# MASTER_HW.net
KiCad netlist of a schematic drawn in Altium Designer
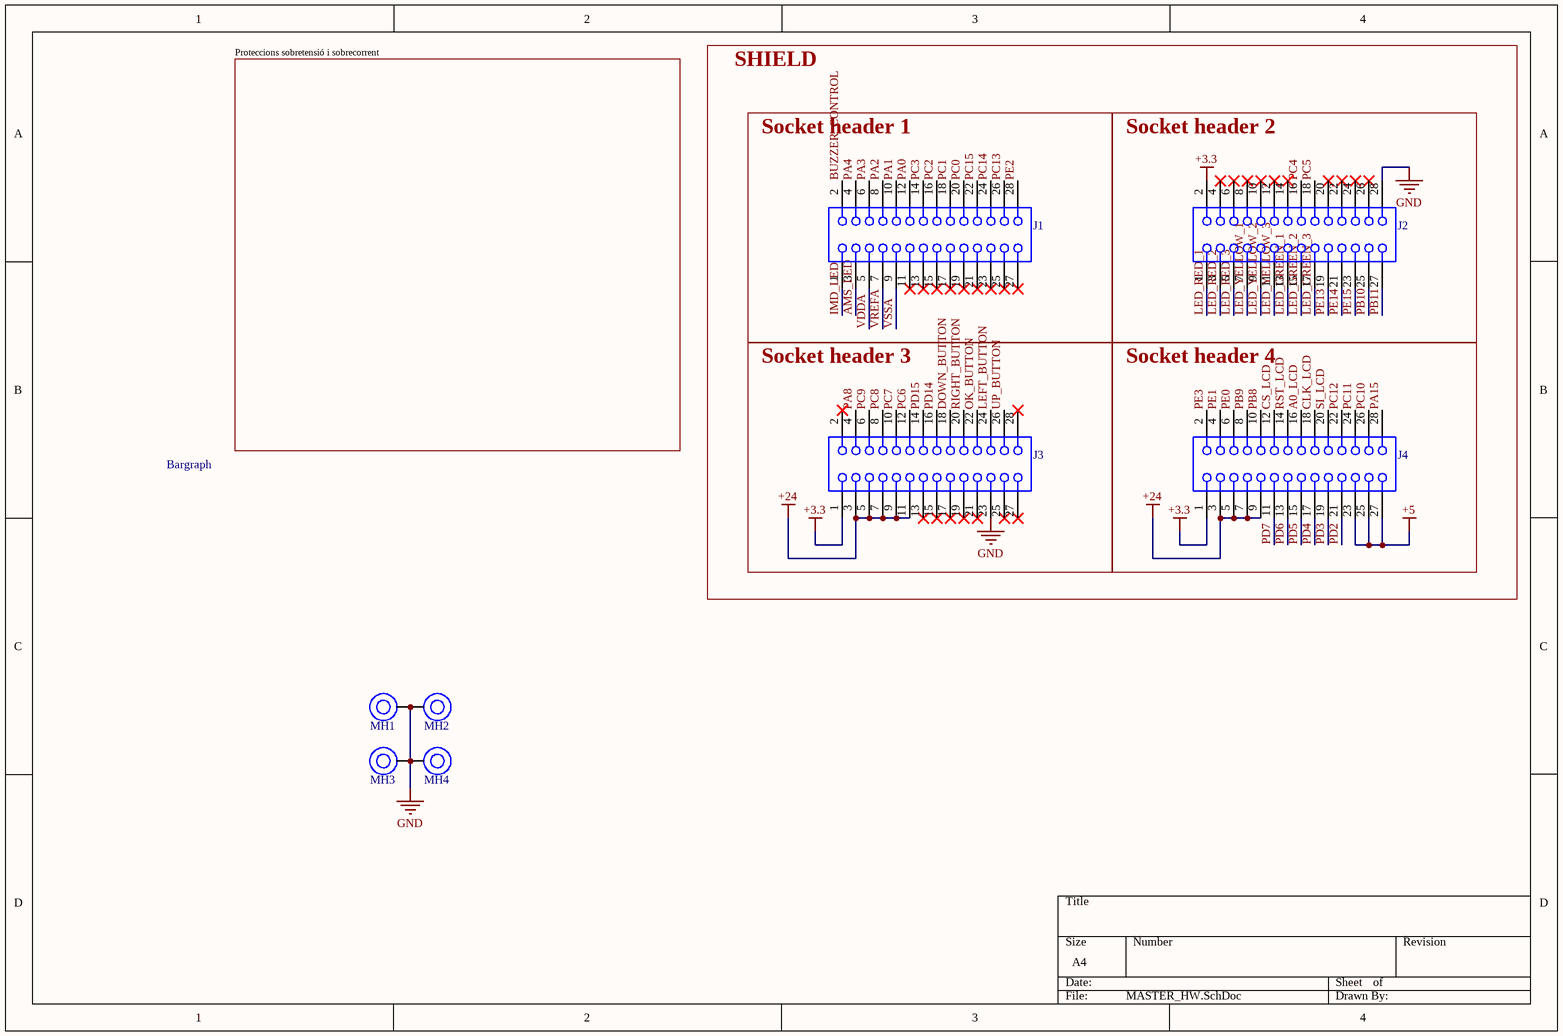
[diagram p0: MASTER_HW.SchDoc]

(export (version "E")
  (design (tool "Eeschema 10.0.6"))
  (components
    (comp (ref "J1")
      (value "62332821021")
      (footprint "62332821021")
      (description "WR-PHD Socket Header, SMT, Vertical, pitch 1.27mm, 2 Row, 28P")
      (fields (field (name "MANUFACTURER") "Wurth Elektronik"))
      (libsource (lib "Electromechanical") (part "62332821021"))
    )
    (comp (ref "J2")
      (value "62332821021")
      (footprint "62332821021")
      (description "WR-PHD Socket Header, SMT, Vertical, pitch 1.27mm, 2 Row, 28P")
      (fields (field (name "MANUFACTURER") "Wurth Elektronik"))
      (libsource (lib "Electromechanical") (part "62332821021"))
    )
    (comp (ref "J3")
      (value "62332821021")
      (footprint "62332821021")
      (description "WR-PHD Socket Header, SMT, Vertical, pitch 1.27mm, 2 Row, 28P")
      (fields (field (name "MANUFACTURER") "Wurth Elektronik"))
      (libsource (lib "Electromechanical") (part "62332821021"))
    )
    (comp (ref "J4")
      (value "62332821021")
      (footprint "62332821021")
      (description "WR-PHD Socket Header, SMT, Vertical, pitch 1.27mm, 2 Row, 28P")
      (fields (field (name "MANUFACTURER") "Wurth Elektronik"))
      (libsource (lib "Electromechanical") (part "62332821021"))
    )
    (comp (ref "MH1")
      (value "Mounting_Hole_M3")
      (footprint "Mounting_Hole_M3")
      (libsource (lib "Electromechanical") (part "Mounting_Hole_M3"))
    )
    (comp (ref "MH2")
      (value "Mounting_Hole_M3")
      (footprint "Mounting_Hole_M3")
      (libsource (lib "Electromechanical") (part "Mounting_Hole_M3"))
    )
    (comp (ref "MH3")
      (value "Mounting_Hole_M3")
      (footprint "Mounting_Hole_M3")
      (libsource (lib "Electromechanical") (part "Mounting_Hole_M3"))
    )
    (comp (ref "MH4")
      (value "Mounting_Hole_M3")
      (footprint "Mounting_Hole_M3")
      (libsource (lib "Electromechanical") (part "Mounting_Hole_M3"))
    )
  )
  (nets
    (net (code "1") (name "+3.3") (class "Default")
      (node (ref "J2") (pin "2") (pinfunction "2_2") (pintype "passive"))
      (node (ref "J3") (pin "1") (pinfunction "1_1") (pintype "passive"))
      (node (ref "J4") (pin "1") (pinfunction "1_1") (pintype "passive"))
    )
    (net (code "2") (name "+5") (class "Default")
      (node (ref "J4") (pin "23") (pinfunction "23_23") (pintype "passive"))
      (node (ref "J4") (pin "25") (pinfunction "25_25") (pintype "passive"))
      (node (ref "J4") (pin "27") (pinfunction "27_27") (pintype "passive"))
    )
    (net (code "3") (name "+24") (class "Default")
      (node (ref "J3") (pin "11") (pinfunction "11_11") (pintype "passive"))
      (node (ref "J3") (pin "3") (pinfunction "3_3") (pintype "passive"))
      (node (ref "J3") (pin "5") (pinfunction "5_5") (pintype "passive"))
      (node (ref "J3") (pin "7") (pinfunction "7_7") (pintype "passive"))
      (node (ref "J3") (pin "9") (pinfunction "9_9") (pintype "passive"))
      (node (ref "J4") (pin "3") (pinfunction "3_3") (pintype "passive"))
      (node (ref "J4") (pin "5") (pinfunction "5_5") (pintype "passive"))
      (node (ref "J4") (pin "7") (pinfunction "7_7") (pintype "passive"))
      (node (ref "J4") (pin "9") (pinfunction "9_9") (pintype "passive"))
    )
    (net (code "4") (name "/A0_LCD") (class "Default")
      (node (ref "J4") (pin "16") (pinfunction "16_16") (pintype "passive"))
    )
    (net (code "5") (name "/AMS_LED") (class "Default")
      (node (ref "J1") (pin "3") (pinfunction "3_3") (pintype "passive"))
    )
    (net (code "6") (name "/BUZZER_CONTROL") (class "Default")
      (node (ref "J1") (pin "2") (pinfunction "2_2") (pintype "passive"))
    )
    (net (code "7") (name "/CLK_LCD") (class "Default")
      (node (ref "J4") (pin "18") (pinfunction "18_18") (pintype "passive"))
    )
    (net (code "8") (name "/CS_LCD") (class "Default")
      (node (ref "J4") (pin "12") (pinfunction "12_12") (pintype "passive"))
    )
    (net (code "9") (name "/DOWN_BUTTON") (class "Default")
      (node (ref "J3") (pin "18") (pinfunction "18_18") (pintype "passive"))
    )
    (net (code "10") (name "/IMD_LED") (class "Default")
      (node (ref "J1") (pin "1") (pinfunction "1_1") (pintype "passive"))
    )
    (net (code "11") (name "/LED_GREEN_1") (class "Default")
      (node (ref "J2") (pin "13") (pinfunction "13_13") (pintype "passive"))
    )
    (net (code "12") (name "/LED_GREEN_2") (class "Default")
      (node (ref "J2") (pin "15") (pinfunction "15_15") (pintype "passive"))
    )
    (net (code "13") (name "/LED_GREEN_3") (class "Default")
      (node (ref "J2") (pin "17") (pinfunction "17_17") (pintype "passive"))
    )
    (net (code "14") (name "/LED_RED_1") (class "Default")
      (node (ref "J2") (pin "1") (pinfunction "1_1") (pintype "passive"))
    )
    (net (code "15") (name "/LED_RED_2") (class "Default")
      (node (ref "J2") (pin "3") (pinfunction "3_3") (pintype "passive"))
    )
    (net (code "16") (name "/LED_RED_3") (class "Default")
      (node (ref "J2") (pin "5") (pinfunction "5_5") (pintype "passive"))
    )
    (net (code "17") (name "/LED_YELLOW_1") (class "Default")
      (node (ref "J2") (pin "7") (pinfunction "7_7") (pintype "passive"))
    )
    (net (code "18") (name "/LED_YELLOW_2") (class "Default")
      (node (ref "J2") (pin "9") (pinfunction "9_9") (pintype "passive"))
    )
    (net (code "19") (name "/LED_YELLOW_3") (class "Default")
      (node (ref "J2") (pin "11") (pinfunction "11_11") (pintype "passive"))
    )
    (net (code "20") (name "/LEFT_BUTTON") (class "Default")
      (node (ref "J3") (pin "24") (pinfunction "24_24") (pintype "passive"))
    )
    (net (code "21") (name "/OK_BUTTON") (class "Default")
      (node (ref "J3") (pin "22") (pinfunction "22_22") (pintype "passive"))
    )
    (net (code "22") (name "/PA0") (class "Default")
      (node (ref "J1") (pin "12") (pinfunction "12_12") (pintype "passive"))
    )
    (net (code "23") (name "/PA1") (class "Default")
      (node (ref "J1") (pin "10") (pinfunction "10_10") (pintype "passive"))
    )
    (net (code "24") (name "/PA2") (class "Default")
      (node (ref "J1") (pin "8") (pinfunction "8_8") (pintype "passive"))
    )
    (net (code "25") (name "/PA3") (class "Default")
      (node (ref "J1") (pin "6") (pinfunction "6_6") (pintype "passive"))
    )
    (net (code "26") (name "/PA4") (class "Default")
      (node (ref "J1") (pin "4") (pinfunction "4_4") (pintype "passive"))
    )
    (net (code "27") (name "/PA8") (class "Default")
      (node (ref "J3") (pin "4") (pinfunction "4_4") (pintype "passive"))
    )
    (net (code "28") (name "/PA15") (class "Default")
      (node (ref "J4") (pin "28") (pinfunction "28_28") (pintype "passive"))
    )
    (net (code "29") (name "/PB8") (class "Default")
      (node (ref "J4") (pin "10") (pinfunction "10_10") (pintype "passive"))
    )
    (net (code "30") (name "/PB9") (class "Default")
      (node (ref "J4") (pin "8") (pinfunction "8_8") (pintype "passive"))
    )
    (net (code "31") (name "/PB10") (class "Default")
      (node (ref "J2") (pin "25") (pinfunction "25_25") (pintype "passive"))
    )
    (net (code "32") (name "/PB11") (class "Default")
      (node (ref "J2") (pin "27") (pinfunction "27_27") (pintype "passive"))
    )
    (net (code "33") (name "/PC0") (class "Default")
      (node (ref "J1") (pin "20") (pinfunction "20_20") (pintype "passive"))
    )
    (net (code "34") (name "/PC1") (class "Default")
      (node (ref "J1") (pin "18") (pinfunction "18_18") (pintype "passive"))
    )
    (net (code "35") (name "/PC2") (class "Default")
      (node (ref "J1") (pin "16") (pinfunction "16_16") (pintype "passive"))
    )
    (net (code "36") (name "/PC3") (class "Default")
      (node (ref "J1") (pin "14") (pinfunction "14_14") (pintype "passive"))
    )
    (net (code "37") (name "/PC4") (class "Default")
      (node (ref "J2") (pin "16") (pinfunction "16_16") (pintype "passive"))
    )
    (net (code "38") (name "/PC5") (class "Default")
      (node (ref "J2") (pin "18") (pinfunction "18_18") (pintype "passive"))
    )
    (net (code "39") (name "/PC6") (class "Default")
      (node (ref "J3") (pin "12") (pinfunction "12_12") (pintype "passive"))
    )
    (net (code "40") (name "/PC7") (class "Default")
      (node (ref "J3") (pin "10") (pinfunction "10_10") (pintype "passive"))
    )
    (net (code "41") (name "/PC8") (class "Default")
      (node (ref "J3") (pin "8") (pinfunction "8_8") (pintype "passive"))
    )
    (net (code "42") (name "/PC9") (class "Default")
      (node (ref "J3") (pin "6") (pinfunction "6_6") (pintype "passive"))
    )
    (net (code "43") (name "/PC10") (class "Default")
      (node (ref "J4") (pin "26") (pinfunction "26_26") (pintype "passive"))
    )
    (net (code "44") (name "/PC11") (class "Default")
      (node (ref "J4") (pin "24") (pinfunction "24_24") (pintype "passive"))
    )
    (net (code "45") (name "/PC12") (class "Default")
      (node (ref "J4") (pin "22") (pinfunction "22_22") (pintype "passive"))
    )
    (net (code "46") (name "/PC13") (class "Default")
      (node (ref "J1") (pin "26") (pinfunction "26_26") (pintype "passive"))
    )
    (net (code "47") (name "/PC14") (class "Default")
      (node (ref "J1") (pin "24") (pinfunction "24_24") (pintype "passive"))
    )
    (net (code "48") (name "/PC15") (class "Default")
      (node (ref "J1") (pin "22") (pinfunction "22_22") (pintype "passive"))
    )
    (net (code "49") (name "/PD2") (class "Default")
      (node (ref "J4") (pin "21") (pinfunction "21_21") (pintype "passive"))
    )
    (net (code "50") (name "/PD3") (class "Default")
      (node (ref "J4") (pin "19") (pinfunction "19_19") (pintype "passive"))
    )
    (net (code "51") (name "/PD4") (class "Default")
      (node (ref "J4") (pin "17") (pinfunction "17_17") (pintype "passive"))
    )
    (net (code "52") (name "/PD5") (class "Default")
      (node (ref "J4") (pin "15") (pinfunction "15_15") (pintype "passive"))
    )
    (net (code "53") (name "/PD6") (class "Default")
      (node (ref "J4") (pin "13") (pinfunction "13_13") (pintype "passive"))
    )
    (net (code "54") (name "/PD7") (class "Default")
      (node (ref "J4") (pin "11") (pinfunction "11_11") (pintype "passive"))
    )
    (net (code "55") (name "/PD14") (class "Default")
      (node (ref "J3") (pin "16") (pinfunction "16_16") (pintype "passive"))
    )
    (net (code "56") (name "/PD15") (class "Default")
      (node (ref "J3") (pin "14") (pinfunction "14_14") (pintype "passive"))
    )
    (net (code "57") (name "/PE0") (class "Default")
      (node (ref "J4") (pin "6") (pinfunction "6_6") (pintype "passive"))
    )
    (net (code "58") (name "/PE1") (class "Default")
      (node (ref "J4") (pin "4") (pinfunction "4_4") (pintype "passive"))
    )
    (net (code "59") (name "/PE2") (class "Default")
      (node (ref "J1") (pin "28") (pinfunction "28_28") (pintype "passive"))
    )
    (net (code "60") (name "/PE3") (class "Default")
      (node (ref "J4") (pin "2") (pinfunction "2_2") (pintype "passive"))
    )
    (net (code "61") (name "/PE13") (class "Default")
      (node (ref "J2") (pin "19") (pinfunction "19_19") (pintype "passive"))
    )
    (net (code "62") (name "/PE14") (class "Default")
      (node (ref "J2") (pin "21") (pinfunction "21_21") (pintype "passive"))
    )
    (net (code "63") (name "/PE15") (class "Default")
      (node (ref "J2") (pin "23") (pinfunction "23_23") (pintype "passive"))
    )
    (net (code "64") (name "/RIGHT_BUTTON") (class "Default")
      (node (ref "J3") (pin "20") (pinfunction "20_20") (pintype "passive"))
    )
    (net (code "65") (name "/RST_LCD") (class "Default")
      (node (ref "J4") (pin "14") (pinfunction "14_14") (pintype "passive"))
    )
    (net (code "66") (name "/SI_LCD") (class "Default")
      (node (ref "J4") (pin "20") (pinfunction "20_20") (pintype "passive"))
    )
    (net (code "67") (name "/UP_BUTTON") (class "Default")
      (node (ref "J3") (pin "26") (pinfunction "26_26") (pintype "passive"))
    )
    (net (code "68") (name "/VDDA") (class "Default")
      (node (ref "J1") (pin "5") (pinfunction "5_5") (pintype "passive"))
    )
    (net (code "69") (name "/VREFA") (class "Default")
      (node (ref "J1") (pin "7") (pinfunction "7_7") (pintype "passive"))
    )
    (net (code "70") (name "/VSSA") (class "Default")
      (node (ref "J1") (pin "9") (pinfunction "9_9") (pintype "passive"))
    )
    (net (code "71") (name "GND") (class "Default")
      (node (ref "J2") (pin "28") (pinfunction "28_28") (pintype "passive"))
      (node (ref "J3") (pin "23") (pinfunction "23_23") (pintype "passive"))
      (node (ref "MH1") (pin "1") (pinfunction "1_1") (pintype "passive"))
      (node (ref "MH2") (pin "1") (pinfunction "1_1") (pintype "passive"))
      (node (ref "MH3") (pin "1") (pinfunction "1_1") (pintype "passive"))
      (node (ref "MH4") (pin "1") (pinfunction "1_1") (pintype "passive"))
    )
    (net (code "72") (name "unconnected-(J1-Pad11)") (class "Default")
      (node (ref "J1") (pin "11") (pinfunction "11_11") (pintype "passive+no_connect"))
    )
    (net (code "73") (name "unconnected-(J1-Pad13)") (class "Default")
      (node (ref "J1") (pin "13") (pinfunction "13_13") (pintype "passive+no_connect"))
    )
    (net (code "74") (name "unconnected-(J1-Pad15)") (class "Default")
      (node (ref "J1") (pin "15") (pinfunction "15_15") (pintype "passive+no_connect"))
    )
    (net (code "75") (name "unconnected-(J1-Pad17)") (class "Default")
      (node (ref "J1") (pin "17") (pinfunction "17_17") (pintype "passive+no_connect"))
    )
    (net (code "76") (name "unconnected-(J1-Pad19)") (class "Default")
      (node (ref "J1") (pin "19") (pinfunction "19_19") (pintype "passive+no_connect"))
    )
    (net (code "77") (name "unconnected-(J1-Pad21)") (class "Default")
      (node (ref "J1") (pin "21") (pinfunction "21_21") (pintype "passive+no_connect"))
    )
    (net (code "78") (name "unconnected-(J1-Pad23)") (class "Default")
      (node (ref "J1") (pin "23") (pinfunction "23_23") (pintype "passive+no_connect"))
    )
    (net (code "79") (name "unconnected-(J1-Pad25)") (class "Default")
      (node (ref "J1") (pin "25") (pinfunction "25_25") (pintype "passive+no_connect"))
    )
    (net (code "80") (name "unconnected-(J1-Pad27)") (class "Default")
      (node (ref "J1") (pin "27") (pinfunction "27_27") (pintype "passive+no_connect"))
    )
    (net (code "81") (name "unconnected-(J2-Pad4)") (class "Default")
      (node (ref "J2") (pin "4") (pinfunction "4_4") (pintype "passive+no_connect"))
    )
    (net (code "82") (name "unconnected-(J2-Pad6)") (class "Default")
      (node (ref "J2") (pin "6") (pinfunction "6_6") (pintype "passive+no_connect"))
    )
    (net (code "83") (name "unconnected-(J2-Pad8)") (class "Default")
      (node (ref "J2") (pin "8") (pinfunction "8_8") (pintype "passive+no_connect"))
    )
    (net (code "84") (name "unconnected-(J2-Pad10)") (class "Default")
      (node (ref "J2") (pin "10") (pinfunction "10_10") (pintype "passive+no_connect"))
    )
    (net (code "85") (name "unconnected-(J2-Pad12)") (class "Default")
      (node (ref "J2") (pin "12") (pinfunction "12_12") (pintype "passive+no_connect"))
    )
    (net (code "86") (name "unconnected-(J2-Pad14)") (class "Default")
      (node (ref "J2") (pin "14") (pinfunction "14_14") (pintype "passive+no_connect"))
    )
    (net (code "87") (name "unconnected-(J2-Pad20)") (class "Default")
      (node (ref "J2") (pin "20") (pinfunction "20_20") (pintype "passive+no_connect"))
    )
    (net (code "88") (name "unconnected-(J2-Pad22)") (class "Default")
      (node (ref "J2") (pin "22") (pinfunction "22_22") (pintype "passive+no_connect"))
    )
    (net (code "89") (name "unconnected-(J2-Pad24)") (class "Default")
      (node (ref "J2") (pin "24") (pinfunction "24_24") (pintype "passive+no_connect"))
    )
    (net (code "90") (name "unconnected-(J2-Pad26)") (class "Default")
      (node (ref "J2") (pin "26") (pinfunction "26_26") (pintype "passive+no_connect"))
    )
    (net (code "91") (name "unconnected-(J3-Pad2)") (class "Default")
      (node (ref "J3") (pin "2") (pinfunction "2_2") (pintype "passive+no_connect"))
    )
    (net (code "92") (name "unconnected-(J3-Pad13)") (class "Default")
      (node (ref "J3") (pin "13") (pinfunction "13_13") (pintype "passive+no_connect"))
    )
    (net (code "93") (name "unconnected-(J3-Pad15)") (class "Default")
      (node (ref "J3") (pin "15") (pinfunction "15_15") (pintype "passive+no_connect"))
    )
    (net (code "94") (name "unconnected-(J3-Pad17)") (class "Default")
      (node (ref "J3") (pin "17") (pinfunction "17_17") (pintype "passive+no_connect"))
    )
    (net (code "95") (name "unconnected-(J3-Pad19)") (class "Default")
      (node (ref "J3") (pin "19") (pinfunction "19_19") (pintype "passive+no_connect"))
    )
    (net (code "96") (name "unconnected-(J3-Pad21)") (class "Default")
      (node (ref "J3") (pin "21") (pinfunction "21_21") (pintype "passive+no_connect"))
    )
    (net (code "97") (name "unconnected-(J3-Pad25)") (class "Default")
      (node (ref "J3") (pin "25") (pinfunction "25_25") (pintype "passive+no_connect"))
    )
    (net (code "98") (name "unconnected-(J3-Pad27)") (class "Default")
      (node (ref "J3") (pin "27") (pinfunction "27_27") (pintype "passive+no_connect"))
    )
    (net (code "99") (name "unconnected-(J3-Pad28)") (class "Default")
      (node (ref "J3") (pin "28") (pinfunction "28_28") (pintype "passive+no_connect"))
    )
  )
)
